# 07_EL_CON.net
KiCad netlist of a schematic drawn in Altium Designer
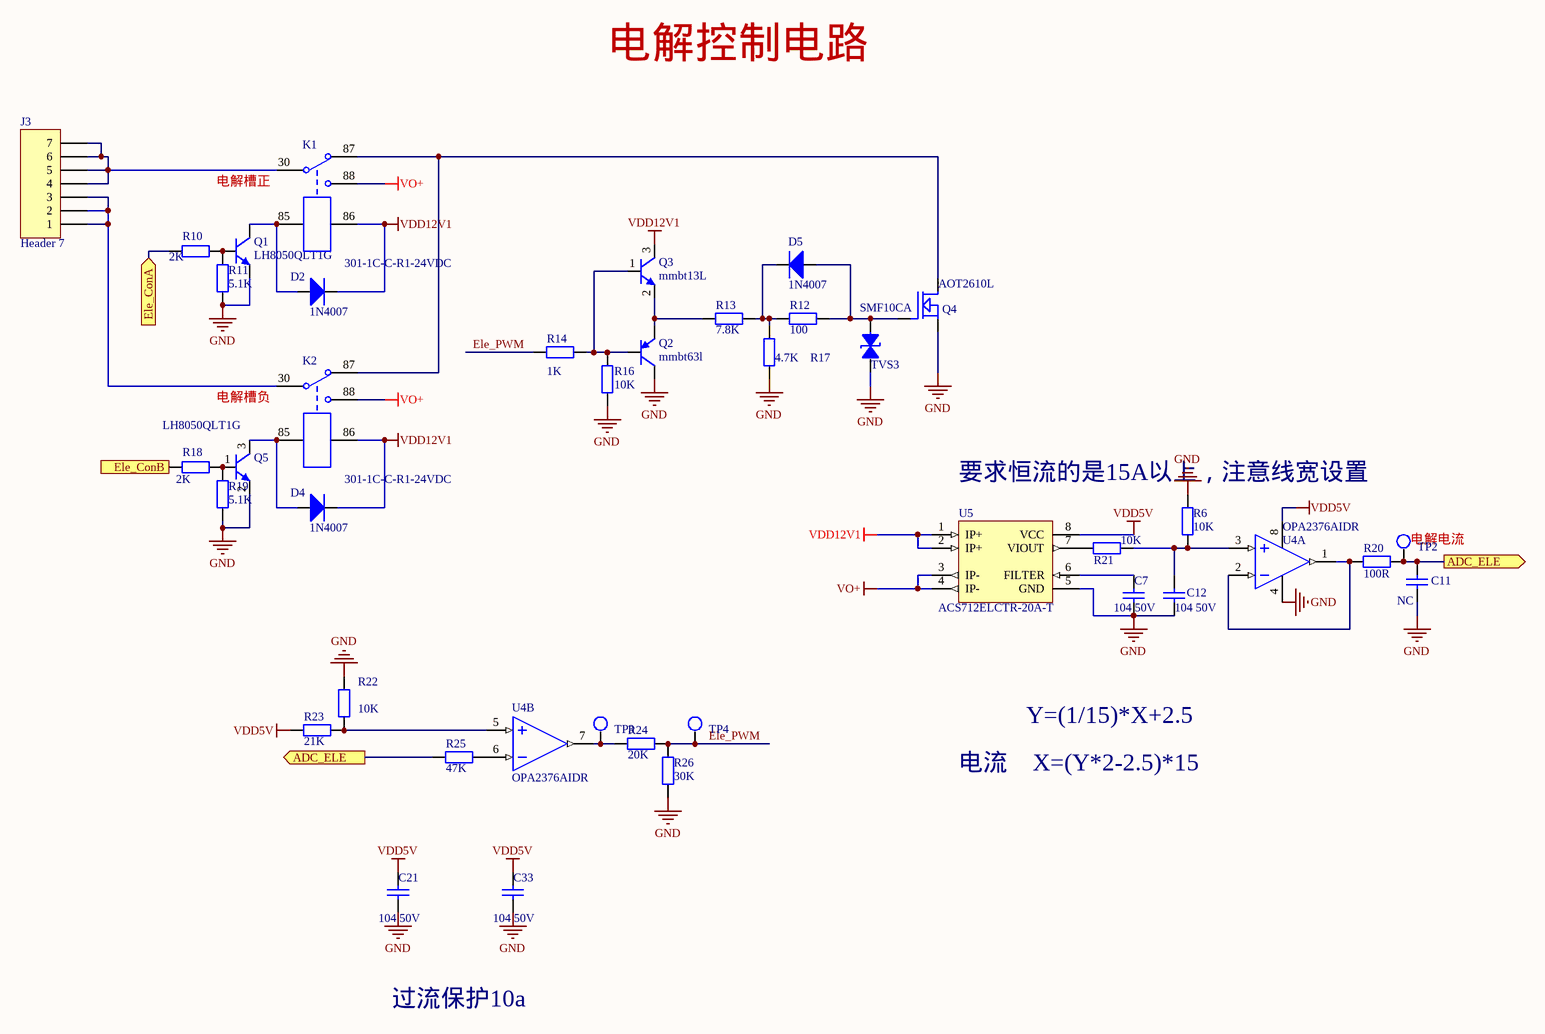
[diagram p0: 07_EL_CON.SchDoc]

(export (version "E")
  (design (tool "Eeschema 10.0.6"))
  (components
    (comp (ref "C7")
      (value "104 50V")
      (footprint "SMD-0603C")
      (description "贴片电容 10%")
      (libsource (lib "XiaoyI") (part "CAP4"))
    )
    (comp (ref "C11")
      (value "NC")
      (footprint "SMD-0603C")
      (description "贴片电容 10%")
      (libsource (lib "XiaoyI") (part "CAP4"))
    )
    (comp (ref "C12")
      (value "104 50V")
      (footprint "SMD-0603C")
      (description "贴片电容 10%")
      (libsource (lib "XiaoyI") (part "CAP4"))
    )
    (comp (ref "C21")
      (value "104 50V")
      (footprint "SMD-0603C")
      (description "贴片电容 20%")
      (libsource (lib "XiaoyI") (part "CAP4"))
    )
    (comp (ref "C33")
      (value "104 50V")
      (footprint "SMD-0603C")
      (description "贴片电容 20%")
      (libsource (lib "XiaoyI") (part "CAP4"))
    )
    (comp (ref "D2")
      (value "1N4007")
      (footprint "DO-214-AC")
      (description "贴片二极管")
      (libsource (lib "XiaoyI") (part "DIODE2"))
    )
    (comp (ref "D4")
      (value "1N4007")
      (footprint "DO-214-AC")
      (description "贴片二极管")
      (libsource (lib "XiaoyI") (part "DIODE2"))
    )
    (comp (ref "D5")
      (value "1N4007")
      (footprint "DO-214-AC")
      (description "贴片二极管")
      (libsource (lib "XiaoyI") (part "DIODE2"))
    )
    (comp (ref "J3")
      (value "Header 7")
      (footprint "VH-AW-3.96*7P")
      (description "Header, 7-Pin")
      (fields (field (name "PUBLISHER") "Altium Limited"))
      (libsource (lib "Miscellaneous Connectors") (part "Header 7"))
    )
    (comp (ref "K1")
      (value "301-1C-C-R1-24VDC")
      (footprint "301-1C-C-R1-24VDC")
      (description "5V 继电器")
      (libsource (lib "XiaoyI") (part "JDQ1"))
    )
    (comp (ref "K2")
      (value "301-1C-C-R1-24VDC")
      (footprint "301-1C-C-R1-24VDC")
      (description "5V 继电器")
      (libsource (lib "XiaoyI") (part "JDQ1"))
    )
    (comp (ref "Q1")
      (value "LH8050QLT1G")
      (footprint "SOT-23")
      (description "三极管")
      (libsource (lib "XiaoyI") (part "NPN-1"))
    )
    (comp (ref "Q2")
      (value "mmbt63l")
      (footprint "SOT-23")
      (description "PNP")
      (libsource (lib "XiaoyI") (part "PNP"))
    )
    (comp (ref "Q3")
      (value "mmbt13L")
      (footprint "SOT-23")
      (description "三极管")
      (libsource (lib "") (part "NPN-1_1"))
    )
    (comp (ref "Q4")
      (value "AOT2610L")
      (footprint "Pcblib_20110825:to220")
      (libsource (lib "POWER") (part "SI7860"))
    )
    (comp (ref "Q5")
      (value "LH8050QLT1G")
      (footprint "SOT-23")
      (description "三极管")
      (libsource (lib "") (part "NPN-1_1"))
    )
    (comp (ref "R6")
      (value "10K")
      (footprint "SMD-0603")
      (description "贴片电阻 1%")
      (libsource (lib "ABB") (part "RES0"))
    )
    (comp (ref "R10")
      (value "2K")
      (footprint "SMD-0603")
      (description "贴片电阻 5%")
      (libsource (lib "XiaoyI") (part "RES2"))
    )
    (comp (ref "R11")
      (value "5.1K")
      (footprint "SMD-0603")
      (description "贴片电阻 5%")
      (libsource (lib "") (part "RES2_1"))
    )
    (comp (ref "R12")
      (value "100")
      (footprint "SMD-0603")
      (description "贴片电阻 5%")
      (libsource (lib "") (part "RES-SOP_1"))
    )
    (comp (ref "R13")
      (value "7.8K")
      (footprint "SMD-0603")
      (description "贴片电阻 5%")
      (libsource (lib "XiaoyI") (part "RES-SOP"))
    )
    (comp (ref "R14")
      (value "1K")
      (footprint "SMD-0603")
      (description "贴片电阻 5%")
      (libsource (lib "XiaoyI") (part "RES-SOP"))
    )
    (comp (ref "R16")
      (value "10K")
      (footprint "SMD-0603")
      (description "贴片电阻 5%")
      (libsource (lib "") (part "RES-SOP_2"))
    )
    (comp (ref "R17")
      (value "4.7K")
      (footprint "SMD-0603")
      (description "贴片电阻 5%")
      (libsource (lib "") (part "RES-SOP_3"))
    )
    (comp (ref "R18")
      (value "2K")
      (footprint "SMD-0603")
      (description "贴片电阻 5%")
      (libsource (lib "XiaoyI") (part "RES2"))
    )
    (comp (ref "R19")
      (value "5.1K")
      (footprint "SMD-0603")
      (description "贴片电阻 5%")
      (libsource (lib "") (part "RES2_1"))
    )
    (comp (ref "R20")
      (value "100R")
      (footprint "SMD-0603")
      (description "贴片电阻 5%")
      (libsource (lib "") (part "RES0_1"))
    )
    (comp (ref "R21")
      (value "10K")
      (footprint "SMD-0603")
      (description "贴片电阻 1%")
      (libsource (lib "") (part "RES0_1"))
    )
    (comp (ref "R22")
      (value "10K")
      (footprint "SMD-0603")
      (description "贴片电阻 5%")
      (libsource (lib "") (part "RES-SOP_2"))
    )
    (comp (ref "R23")
      (value "21K")
      (footprint "SMD-0603")
      (description "贴片电阻 5%")
      (libsource (lib "XiaoyI") (part "RES-SOP"))
    )
    (comp (ref "R24")
      (value "20K")
      (footprint "SMD-0603")
      (description "贴片电阻 5%")
      (libsource (lib "XiaoyI") (part "RES-SOP"))
    )
    (comp (ref "R25")
      (value "47K")
      (footprint "SMD-0603")
      (description "贴片电阻 5%")
      (libsource (lib "XiaoyI") (part "RES-SOP"))
    )
    (comp (ref "R26")
      (value "30K")
      (footprint "SMD-0603")
      (description "贴片电阻 5%")
      (libsource (lib "") (part "RES-SOP_3"))
    )
    (comp (ref "TP2") (value "TPS") (footprint "tpd") (libsource (lib "stm32") (part "TPS")))
    (comp (ref "TP3") (value "TPS") (footprint "tpd") (libsource (lib "stm32") (part "TPS")))
    (comp (ref "TP4") (value "TPS") (footprint "tpd") (libsource (lib "stm32") (part "TPS")))
    (comp (ref "TVS3")
      (value "SMF10CA")
      (footprint "SOD-123")
      (description "TVS 10V")
      (libsource (lib "XiaoyI") (part "TVS-1"))
    )
    (comp (ref "U4")
      (value "OPA2376AIDR")
      (footprint "SO-8")
      (description "运算放大器")
      (libsource (lib "XiaoyI") (part "LM358"))
    )
    (comp (ref "U5")
      (value "ACS712ELCTR-20A-T")
      (footprint "SO-8")
      (description "HALL 20A 电流传感器")
      (libsource (lib "XiaoyI") (part "ACS712"))
    )
  )
  (nets
    (net (code "1") (name "/ADC_ELE") (class "Default")
      (node (ref "C11") (pin "2") (pinfunction "2_2") (pintype "passive"))
      (node (ref "R20") (pin "1") (pinfunction "1_1") (pintype "passive"))
      (node (ref "R25") (pin "2") (pinfunction "2_2") (pintype "passive"))
      (node (ref "TP2") (pin "1") (pinfunction "1_1") (pintype "passive"))
    )
    (net (code "2") (name "/Ele_ConA") (class "Default")
      (node (ref "R10") (pin "1") (pinfunction "1_1") (pintype "passive"))
    )
    (net (code "3") (name "/Ele_ConB") (class "Default")
      (node (ref "R18") (pin "1") (pinfunction "1_1") (pintype "passive"))
    )
    (net (code "4") (name "/Ele_PWM") (class "Default")
      (node (ref "R14") (pin "2") (pinfunction "2_2") (pintype "passive"))
      (node (ref "R24") (pin "1") (pinfunction "1_1") (pintype "passive"))
      (node (ref "R26") (pin "1") (pinfunction "1_1") (pintype "passive"))
      (node (ref "TP4") (pin "1") (pinfunction "1_1") (pintype "passive"))
    )
    (net (code "5") (name "GND") (class "Default")
      (node (ref "C11") (pin "1") (pinfunction "1_1") (pintype "passive"))
      (node (ref "C12") (pin "2") (pinfunction "2_2") (pintype "passive"))
      (node (ref "C21") (pin "1") (pinfunction "1_1") (pintype "passive"))
      (node (ref "C33") (pin "1") (pinfunction "1_1") (pintype "passive"))
      (node (ref "C7") (pin "2") (pinfunction "2_2") (pintype "passive"))
      (node (ref "Q1") (pin "2") (pinfunction "E_2") (pintype "passive"))
      (node (ref "Q2") (pin "3") (pinfunction "C_3") (pintype "passive"))
      (node (ref "Q4") (pin "3") (pinfunction "S_3") (pintype "passive"))
      (node (ref "Q5") (pin "2") (pinfunction "E_2") (pintype "passive"))
      (node (ref "R11") (pin "1") (pinfunction "1_1") (pintype "passive"))
      (node (ref "R16") (pin "1") (pinfunction "1_1") (pintype "passive"))
      (node (ref "R17") (pin "2") (pinfunction "2_2") (pintype "passive"))
      (node (ref "R19") (pin "1") (pinfunction "1_1") (pintype "passive"))
      (node (ref "R22") (pin "2") (pinfunction "2_2") (pintype "passive"))
      (node (ref "R26") (pin "2") (pinfunction "2_2") (pintype "passive"))
      (node (ref "R6") (pin "1") (pinfunction "1_1") (pintype "passive"))
      (node (ref "TVS3") (pin "1") (pinfunction "A_1") (pintype "passive"))
      (node (ref "U4") (pin "4") (pinfunction "V-_4") (pintype "power_in"))
      (node (ref "U5") (pin "5") (pinfunction "GND_5") (pintype "power_in"))
    )
    (net (code "6") (name "Net-(D2-A)") (class "Default")
      (node (ref "D2") (pin "1") (pinfunction "A_1") (pintype "passive"))
      (node (ref "K1") (pin "85") (pinfunction "4_85") (pintype "passive"))
      (node (ref "Q1") (pin "3") (pinfunction "C_3") (pintype "passive"))
    )
    (net (code "7") (name "Net-(D4-A)") (class "Default")
      (node (ref "D4") (pin "1") (pinfunction "A_1") (pintype "passive"))
      (node (ref "K2") (pin "85") (pinfunction "4_85") (pintype "passive"))
      (node (ref "Q5") (pin "3") (pinfunction "C_3") (pintype "passive"))
    )
    (net (code "8") (name "Net-(D5-A)") (class "Default")
      (node (ref "D5") (pin "1") (pinfunction "A_1") (pintype "passive"))
      (node (ref "Q4") (pin "1") (pinfunction "G_1") (pintype "passive"))
      (node (ref "R12") (pin "2") (pinfunction "2_2") (pintype "passive"))
      (node (ref "TVS3") (pin "2") (pinfunction "B_2") (pintype "passive"))
    )
    (net (code "9") (name "Net-(D5-K)") (class "Default")
      (node (ref "D5") (pin "2") (pinfunction "K_2") (pintype "passive"))
      (node (ref "R12") (pin "1") (pinfunction "1_1") (pintype "passive"))
      (node (ref "R13") (pin "1") (pinfunction "1_1") (pintype "passive"))
      (node (ref "R17") (pin "1") (pinfunction "1_1") (pintype "passive"))
    )
    (net (code "10") (name "Net-(K1-1)") (class "Default")
      (node (ref "J3") (pin "4") (pinfunction "4_4") (pintype "passive"))
      (node (ref "J3") (pin "5") (pinfunction "5_5") (pintype "passive"))
      (node (ref "J3") (pin "6") (pinfunction "6_6") (pintype "passive"))
      (node (ref "J3") (pin "7") (pinfunction "7_7") (pintype "passive"))
      (node (ref "K1") (pin "30") (pinfunction "1_30") (pintype "passive"))
    )
    (net (code "11") (name "Net-(K1-3)") (class "Default")
      (node (ref "K1") (pin "87") (pinfunction "3_87") (pintype "passive"))
      (node (ref "K2") (pin "87") (pinfunction "3_87") (pintype "passive"))
      (node (ref "Q4") (pin "2") (pinfunction "D_2") (pintype "passive"))
    )
    (net (code "12") (name "Net-(K2-1)") (class "Default")
      (node (ref "J3") (pin "1") (pinfunction "1_1") (pintype "passive"))
      (node (ref "J3") (pin "2") (pinfunction "2_2") (pintype "passive"))
      (node (ref "J3") (pin "3") (pinfunction "3_3") (pintype "passive"))
      (node (ref "K2") (pin "30") (pinfunction "1_30") (pintype "passive"))
    )
    (net (code "13") (name "Net-(Q1-B)") (class "Default")
      (node (ref "Q1") (pin "1") (pinfunction "B_1") (pintype "passive"))
      (node (ref "R10") (pin "2") (pinfunction "2_2") (pintype "passive"))
      (node (ref "R11") (pin "2") (pinfunction "2_2") (pintype "passive"))
    )
    (net (code "14") (name "Net-(Q2-B)") (class "Default")
      (node (ref "Q2") (pin "1") (pinfunction "B_1") (pintype "passive"))
      (node (ref "Q3") (pin "1") (pinfunction "B_1") (pintype "passive"))
      (node (ref "R14") (pin "1") (pinfunction "1_1") (pintype "passive"))
      (node (ref "R16") (pin "2") (pinfunction "2_2") (pintype "passive"))
    )
    (net (code "15") (name "Net-(Q2-E)") (class "Default")
      (node (ref "Q2") (pin "2") (pinfunction "E_2") (pintype "passive"))
      (node (ref "Q3") (pin "2") (pinfunction "E_2") (pintype "passive"))
      (node (ref "R13") (pin "2") (pinfunction "2_2") (pintype "passive"))
    )
    (net (code "16") (name "Net-(Q5-B)") (class "Default")
      (node (ref "Q5") (pin "1") (pinfunction "B_1") (pintype "passive"))
      (node (ref "R18") (pin "2") (pinfunction "2_2") (pintype "passive"))
      (node (ref "R19") (pin "2") (pinfunction "2_2") (pintype "passive"))
    )
    (net (code "17") (name "Net-(U4A-IN1+)") (class "Default")
      (node (ref "C12") (pin "1") (pinfunction "1_1") (pintype "passive"))
      (node (ref "R21") (pin "1") (pinfunction "1_1") (pintype "passive"))
      (node (ref "R6") (pin "2") (pinfunction "2_2") (pintype "passive"))
      (node (ref "U4") (pin "3") (pinfunction "IN1+_3") (pintype "input"))
    )
    (net (code "18") (name "Net-(U4A-IN1-)") (class "Default")
      (node (ref "R20") (pin "2") (pinfunction "2_2") (pintype "passive"))
      (node (ref "U4") (pin "1") (pinfunction "OUT1_1") (pintype "output"))
      (node (ref "U4") (pin "2") (pinfunction "IN1-_2") (pintype "input"))
    )
    (net (code "19") (name "Net-(U4B-IN2+)") (class "Default")
      (node (ref "R22") (pin "1") (pinfunction "1_1") (pintype "passive"))
      (node (ref "R23") (pin "1") (pinfunction "1_1") (pintype "passive"))
      (node (ref "U4") (pin "5") (pinfunction "IN2+_5") (pintype "input"))
    )
    (net (code "20") (name "Net-(U4B-IN2-)") (class "Default")
      (node (ref "R25") (pin "1") (pinfunction "1_1") (pintype "passive"))
      (node (ref "U4") (pin "6") (pinfunction "IN2-_6") (pintype "input"))
    )
    (net (code "21") (name "Net-(U4B-OUT2)") (class "Default")
      (node (ref "R24") (pin "2") (pinfunction "2_2") (pintype "passive"))
      (node (ref "TP3") (pin "1") (pinfunction "1_1") (pintype "passive"))
      (node (ref "U4") (pin "7") (pinfunction "OUT2_7") (pintype "output"))
    )
    (net (code "22") (name "Net-(U5-FILTER)") (class "Default")
      (node (ref "C7") (pin "1") (pinfunction "1_1") (pintype "passive"))
      (node (ref "U5") (pin "6") (pinfunction "FILTER_6") (pintype "input"))
    )
    (net (code "23") (name "Net-(U5-VIOUT)") (class "Default")
      (node (ref "R21") (pin "2") (pinfunction "2_2") (pintype "passive"))
      (node (ref "U5") (pin "7") (pinfunction "VIOUT_7") (pintype "output"))
    )
    (net (code "24") (name "VDD5V") (class "Default")
      (node (ref "C21") (pin "2") (pinfunction "2_2") (pintype "passive"))
      (node (ref "C33") (pin "2") (pinfunction "2_2") (pintype "passive"))
      (node (ref "R23") (pin "2") (pinfunction "2_2") (pintype "passive"))
      (node (ref "U4") (pin "8") (pinfunction "V+_8") (pintype "power_in"))
      (node (ref "U5") (pin "8") (pinfunction "VCC_8") (pintype "power_in"))
    )
    (net (code "25") (name "VDD12V1") (class "Default")
      (node (ref "D2") (pin "2") (pinfunction "K_2") (pintype "passive"))
      (node (ref "D4") (pin "2") (pinfunction "K_2") (pintype "passive"))
      (node (ref "K1") (pin "86") (pinfunction "5_86") (pintype "passive"))
      (node (ref "K2") (pin "86") (pinfunction "5_86") (pintype "passive"))
      (node (ref "Q3") (pin "3") (pinfunction "C_3") (pintype "passive"))
      (node (ref "U5") (pin "1") (pinfunction "IP+_1") (pintype "input"))
      (node (ref "U5") (pin "2") (pinfunction "IP+_2") (pintype "input"))
    )
    (net (code "26") (name "VO+") (class "Default")
      (node (ref "K1") (pin "88") (pinfunction "2_88") (pintype "passive"))
      (node (ref "K2") (pin "88") (pinfunction "2_88") (pintype "passive"))
      (node (ref "U5") (pin "3") (pinfunction "IP-_3") (pintype "output"))
      (node (ref "U5") (pin "4") (pinfunction "IP-_4") (pintype "output"))
    )
  )
)
